# Module32Switches_SM.net
KiCad netlist of a schematic drawn in EasyEDA Pro
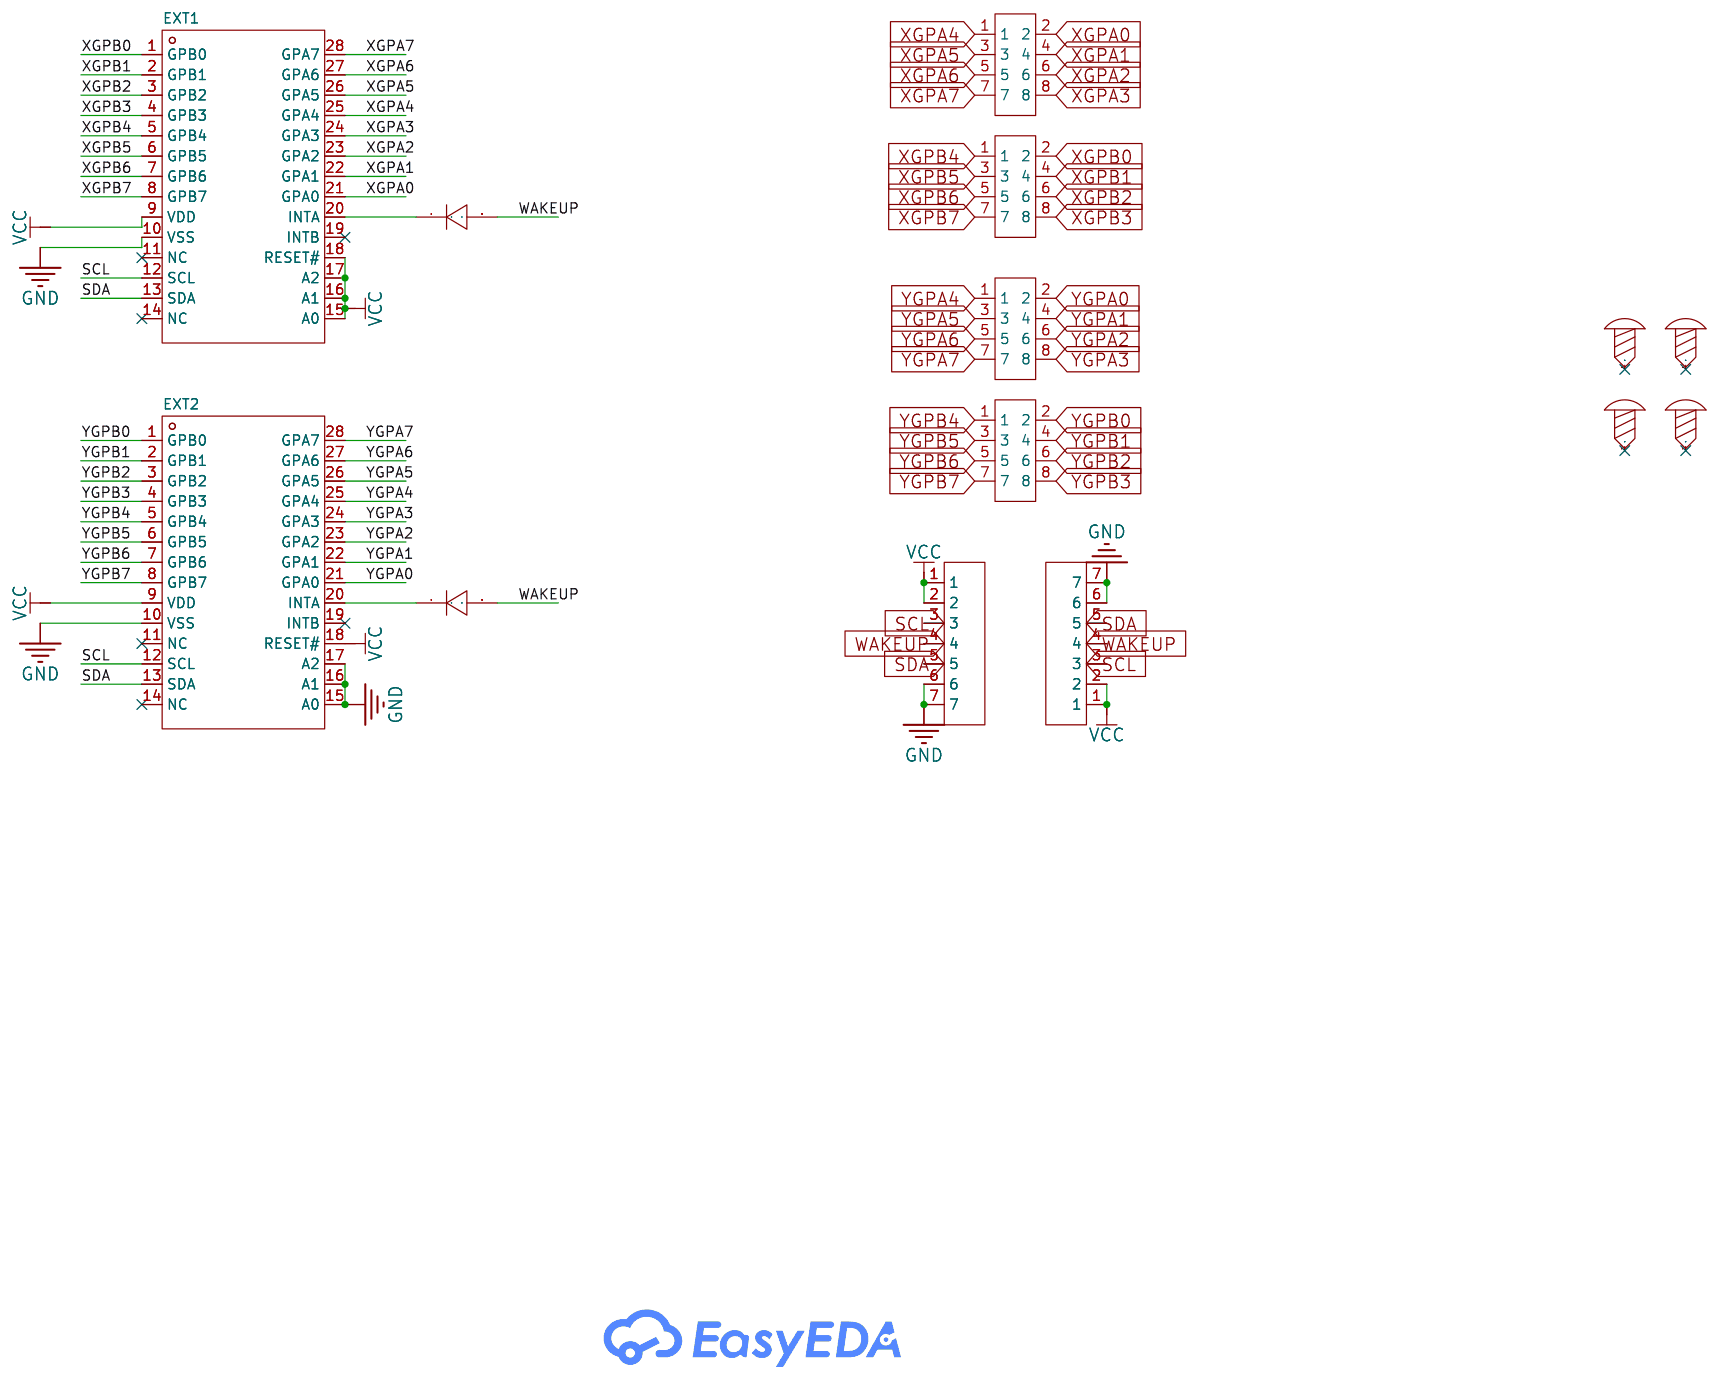
[diagram p0: schematic sheet]

(export (version "E")
  (design (tool "Eeschema 10.0.6"))
  (components
    (comp (ref "D1")
      (value "1N4148W")
      (footprint "easyedapro:SOD-123FL_L2.7-W1.6-LS3.8-RD")
      (fields (field (name "Manufacturer") "ST(先科)"))
      (libsource (lib "easyedapro") (part "1N4148W_C143180"))
    )
    (comp (ref "D2")
      (value "1N4148W")
      (footprint "easyedapro:SOD-123FL_L2.7-W1.6-LS3.8-RD")
      (fields (field (name "Manufacturer") "ST(先科)"))
      (libsource (lib "easyedapro") (part "1N4148W_C143180"))
    )
    (comp (ref "DEVKIT1")
      (value "~")
      (footprint "easyedapro:HDR-TH_7P-P2.54-V-M")
      (libsource (lib "easyedapro") (part "PZ254V-11-07P"))
    )
    (comp (ref "DEVKIT2")
      (value "~")
      (footprint "easyedapro:HDR-TH_7P-P2.54-V-M")
      (libsource (lib "easyedapro") (part "PZ254V-11-07P"))
    )
    (comp (ref "EXT1")
      (value "MCP23017T-E/ML")
      (footprint "easyedapro:SOIC-28_L18.0-W7.5-P1.27-LS10.3-BL")
      (fields (field (name "Manufacturer") "MICROCHIP(美国微芯)"))
      (libsource (lib "easyedapro") (part "MCP23017-E/SO"))
    )
    (comp (ref "EXT2")
      (value "MCP23017T-E/ML")
      (footprint "easyedapro:SOIC-28_L18.0-W7.5-P1.27-LS10.3-BL")
      (fields (field (name "Manufacturer") "MICROCHIP(美国微芯)"))
      (libsource (lib "easyedapro") (part "MCP23017-E/SO"))
    )
    (comp (ref "SCREW1")
      (value "~")
      (footprint "easyedapro:Screw-Hole-M2")
      (libsource (lib "easyedapro") (part "Screw-Hole"))
    )
    (comp (ref "SCREW2")
      (value "~")
      (footprint "easyedapro:Screw-Hole-M2")
      (libsource (lib "easyedapro") (part "Screw-Hole"))
    )
    (comp (ref "SCREW3")
      (value "~")
      (footprint "easyedapro:Screw-Hole-M2")
      (libsource (lib "easyedapro") (part "Screw-Hole"))
    )
    (comp (ref "SCREW4")
      (value "~")
      (footprint "easyedapro:Screw-Hole-M2")
      (libsource (lib "easyedapro") (part "Screw-Hole"))
    )
    (comp (ref "XH1")
      (value "PZ254R-12-8P")
      (footprint "easyedapro:HDR-TH_8P-P2.54-H-M-R2-C4-S2.54")
      (fields (field (name "Manufacturer") "XFCN(兴飞)"))
      (libsource (lib "easyedapro") (part "PZ254R-12-8P"))
    )
    (comp (ref "XH2")
      (value "PZ254R-12-8P")
      (footprint "easyedapro:HDR-TH_8P-P2.54-H-M-R2-C4-S2.54")
      (fields (field (name "Manufacturer") "XFCN(兴飞)"))
      (libsource (lib "easyedapro") (part "PZ254R-12-8P"))
    )
    (comp (ref "YH1")
      (value "PZ254R-12-8P")
      (footprint "easyedapro:HDR-TH_8P-P2.54-H-M-R2-C4-S2.54")
      (fields (field (name "Manufacturer") "XFCN(兴飞)"))
      (libsource (lib "easyedapro") (part "PZ254R-12-8P"))
    )
    (comp (ref "YH2")
      (value "PZ254R-12-8P")
      (footprint "easyedapro:HDR-TH_8P-P2.54-H-M-R2-C4-S2.54")
      (fields (field (name "Manufacturer") "XFCN(兴飞)"))
      (libsource (lib "easyedapro") (part "PZ254R-12-8P"))
    )
  )
  (nets
    (net (code "1") (name "GND") (class "Default")
      (node (ref "DEVKIT1") (pin "6") (pinfunction "6_6") (pintype "unspecified"))
      (node (ref "DEVKIT1") (pin "7") (pinfunction "7_7") (pintype "unspecified"))
      (node (ref "DEVKIT2") (pin "6") (pinfunction "6_6") (pintype "unspecified"))
      (node (ref "DEVKIT2") (pin "7") (pinfunction "7_7") (pintype "unspecified"))
      (node (ref "EXT1") (pin "10") (pinfunction "VSS_10") (pintype "unspecified"))
      (node (ref "EXT2") (pin "10") (pinfunction "VSS_10") (pintype "unspecified"))
      (node (ref "EXT2") (pin "15") (pinfunction "A0_15") (pintype "unspecified"))
      (node (ref "EXT2") (pin "16") (pinfunction "A1_16") (pintype "unspecified"))
      (node (ref "EXT2") (pin "17") (pinfunction "A2_17") (pintype "unspecified"))
    )
    (net (code "2") (name "Net-(D1-K)") (class "Default")
      (node (ref "D1") (pin "1") (pinfunction "K_1") (pintype "unspecified"))
      (node (ref "EXT1") (pin "20") (pinfunction "INTA_20") (pintype "unspecified"))
    )
    (net (code "3") (name "Net-(D2-K)") (class "Default")
      (node (ref "D2") (pin "1") (pinfunction "K_1") (pintype "unspecified"))
      (node (ref "EXT2") (pin "20") (pinfunction "INTA_20") (pintype "unspecified"))
    )
    (net (code "4") (name "SCL") (class "Default")
      (node (ref "DEVKIT1") (pin "3") (pinfunction "3_3") (pintype "unspecified"))
      (node (ref "DEVKIT2") (pin "3") (pinfunction "3_3") (pintype "unspecified"))
      (node (ref "EXT1") (pin "12") (pinfunction "SCL_12") (pintype "unspecified"))
      (node (ref "EXT2") (pin "12") (pinfunction "SCL_12") (pintype "unspecified"))
    )
    (net (code "5") (name "SDA") (class "Default")
      (node (ref "DEVKIT1") (pin "5") (pinfunction "5_5") (pintype "unspecified"))
      (node (ref "DEVKIT2") (pin "5") (pinfunction "5_5") (pintype "unspecified"))
      (node (ref "EXT1") (pin "13") (pinfunction "SDA_13") (pintype "unspecified"))
      (node (ref "EXT2") (pin "13") (pinfunction "SDA_13") (pintype "unspecified"))
    )
    (net (code "6") (name "VCC") (class "Default")
      (node (ref "DEVKIT1") (pin "1") (pinfunction "1_1") (pintype "unspecified"))
      (node (ref "DEVKIT1") (pin "2") (pinfunction "2_2") (pintype "unspecified"))
      (node (ref "DEVKIT2") (pin "1") (pinfunction "1_1") (pintype "unspecified"))
      (node (ref "DEVKIT2") (pin "2") (pinfunction "2_2") (pintype "unspecified"))
      (node (ref "EXT1") (pin "15") (pinfunction "A0_15") (pintype "unspecified"))
      (node (ref "EXT1") (pin "16") (pinfunction "A1_16") (pintype "unspecified"))
      (node (ref "EXT1") (pin "17") (pinfunction "A2_17") (pintype "unspecified"))
      (node (ref "EXT1") (pin "18") (pinfunction "RESET#_18") (pintype "unspecified"))
      (node (ref "EXT1") (pin "9") (pinfunction "VDD_9") (pintype "unspecified"))
      (node (ref "EXT2") (pin "18") (pinfunction "RESET#_18") (pintype "unspecified"))
      (node (ref "EXT2") (pin "9") (pinfunction "VDD_9") (pintype "unspecified"))
    )
    (net (code "7") (name "WAKEUP") (class "Default")
      (node (ref "D1") (pin "2") (pinfunction "A_2") (pintype "unspecified"))
      (node (ref "D2") (pin "2") (pinfunction "A_2") (pintype "unspecified"))
      (node (ref "DEVKIT1") (pin "4") (pinfunction "4_4") (pintype "unspecified"))
      (node (ref "DEVKIT2") (pin "4") (pinfunction "4_4") (pintype "unspecified"))
    )
    (net (code "8") (name "XGPA0") (class "Default")
      (node (ref "EXT1") (pin "21") (pinfunction "GPA0_21") (pintype "unspecified"))
      (node (ref "XH1") (pin "2") (pinfunction "2_2") (pintype "unspecified"))
    )
    (net (code "9") (name "XGPA1") (class "Default")
      (node (ref "EXT1") (pin "22") (pinfunction "GPA1_22") (pintype "unspecified"))
      (node (ref "XH1") (pin "4") (pinfunction "4_4") (pintype "unspecified"))
    )
    (net (code "10") (name "XGPA2") (class "Default")
      (node (ref "EXT1") (pin "23") (pinfunction "GPA2_23") (pintype "unspecified"))
      (node (ref "XH1") (pin "6") (pinfunction "6_6") (pintype "unspecified"))
    )
    (net (code "11") (name "XGPA3") (class "Default")
      (node (ref "EXT1") (pin "24") (pinfunction "GPA3_24") (pintype "unspecified"))
      (node (ref "XH1") (pin "8") (pinfunction "8_8") (pintype "unspecified"))
    )
    (net (code "12") (name "XGPA4") (class "Default")
      (node (ref "EXT1") (pin "25") (pinfunction "GPA4_25") (pintype "unspecified"))
      (node (ref "XH1") (pin "1") (pinfunction "1_1") (pintype "unspecified"))
    )
    (net (code "13") (name "XGPA5") (class "Default")
      (node (ref "EXT1") (pin "26") (pinfunction "GPA5_26") (pintype "unspecified"))
      (node (ref "XH1") (pin "3") (pinfunction "3_3") (pintype "unspecified"))
    )
    (net (code "14") (name "XGPA6") (class "Default")
      (node (ref "EXT1") (pin "27") (pinfunction "GPA6_27") (pintype "unspecified"))
      (node (ref "XH1") (pin "5") (pinfunction "5_5") (pintype "unspecified"))
    )
    (net (code "15") (name "XGPA7") (class "Default")
      (node (ref "EXT1") (pin "28") (pinfunction "GPA7_28") (pintype "unspecified"))
      (node (ref "XH1") (pin "7") (pinfunction "7_7") (pintype "unspecified"))
    )
    (net (code "16") (name "XGPB0") (class "Default")
      (node (ref "EXT1") (pin "1") (pinfunction "GPB0_1") (pintype "unspecified"))
      (node (ref "XH2") (pin "2") (pinfunction "2_2") (pintype "unspecified"))
    )
    (net (code "17") (name "XGPB1") (class "Default")
      (node (ref "EXT1") (pin "2") (pinfunction "GPB1_2") (pintype "unspecified"))
      (node (ref "XH2") (pin "4") (pinfunction "4_4") (pintype "unspecified"))
    )
    (net (code "18") (name "XGPB2") (class "Default")
      (node (ref "EXT1") (pin "3") (pinfunction "GPB2_3") (pintype "unspecified"))
      (node (ref "XH2") (pin "6") (pinfunction "6_6") (pintype "unspecified"))
    )
    (net (code "19") (name "XGPB3") (class "Default")
      (node (ref "EXT1") (pin "4") (pinfunction "GPB3_4") (pintype "unspecified"))
      (node (ref "XH2") (pin "8") (pinfunction "8_8") (pintype "unspecified"))
    )
    (net (code "20") (name "XGPB4") (class "Default")
      (node (ref "EXT1") (pin "5") (pinfunction "GPB4_5") (pintype "unspecified"))
      (node (ref "XH2") (pin "1") (pinfunction "1_1") (pintype "unspecified"))
    )
    (net (code "21") (name "XGPB5") (class "Default")
      (node (ref "EXT1") (pin "6") (pinfunction "GPB5_6") (pintype "unspecified"))
      (node (ref "XH2") (pin "3") (pinfunction "3_3") (pintype "unspecified"))
    )
    (net (code "22") (name "XGPB6") (class "Default")
      (node (ref "EXT1") (pin "7") (pinfunction "GPB6_7") (pintype "unspecified"))
      (node (ref "XH2") (pin "5") (pinfunction "5_5") (pintype "unspecified"))
    )
    (net (code "23") (name "XGPB7") (class "Default")
      (node (ref "EXT1") (pin "8") (pinfunction "GPB7_8") (pintype "unspecified"))
      (node (ref "XH2") (pin "7") (pinfunction "7_7") (pintype "unspecified"))
    )
    (net (code "24") (name "YGPA0") (class "Default")
      (node (ref "EXT2") (pin "21") (pinfunction "GPA0_21") (pintype "unspecified"))
      (node (ref "YH1") (pin "2") (pinfunction "2_2") (pintype "unspecified"))
    )
    (net (code "25") (name "YGPA1") (class "Default")
      (node (ref "EXT2") (pin "22") (pinfunction "GPA1_22") (pintype "unspecified"))
      (node (ref "YH1") (pin "4") (pinfunction "4_4") (pintype "unspecified"))
    )
    (net (code "26") (name "YGPA2") (class "Default")
      (node (ref "EXT2") (pin "23") (pinfunction "GPA2_23") (pintype "unspecified"))
      (node (ref "YH1") (pin "6") (pinfunction "6_6") (pintype "unspecified"))
    )
    (net (code "27") (name "YGPA3") (class "Default")
      (node (ref "EXT2") (pin "24") (pinfunction "GPA3_24") (pintype "unspecified"))
      (node (ref "YH1") (pin "8") (pinfunction "8_8") (pintype "unspecified"))
    )
    (net (code "28") (name "YGPA4") (class "Default")
      (node (ref "EXT2") (pin "25") (pinfunction "GPA4_25") (pintype "unspecified"))
      (node (ref "YH1") (pin "1") (pinfunction "1_1") (pintype "unspecified"))
    )
    (net (code "29") (name "YGPA5") (class "Default")
      (node (ref "EXT2") (pin "26") (pinfunction "GPA5_26") (pintype "unspecified"))
      (node (ref "YH1") (pin "3") (pinfunction "3_3") (pintype "unspecified"))
    )
    (net (code "30") (name "YGPA6") (class "Default")
      (node (ref "EXT2") (pin "27") (pinfunction "GPA6_27") (pintype "unspecified"))
      (node (ref "YH1") (pin "5") (pinfunction "5_5") (pintype "unspecified"))
    )
    (net (code "31") (name "YGPA7") (class "Default")
      (node (ref "EXT2") (pin "28") (pinfunction "GPA7_28") (pintype "unspecified"))
      (node (ref "YH1") (pin "7") (pinfunction "7_7") (pintype "unspecified"))
    )
    (net (code "32") (name "YGPB0") (class "Default")
      (node (ref "EXT2") (pin "1") (pinfunction "GPB0_1") (pintype "unspecified"))
      (node (ref "YH2") (pin "2") (pinfunction "2_2") (pintype "unspecified"))
    )
    (net (code "33") (name "YGPB1") (class "Default")
      (node (ref "EXT2") (pin "2") (pinfunction "GPB1_2") (pintype "unspecified"))
      (node (ref "YH2") (pin "4") (pinfunction "4_4") (pintype "unspecified"))
    )
    (net (code "34") (name "YGPB2") (class "Default")
      (node (ref "EXT2") (pin "3") (pinfunction "GPB2_3") (pintype "unspecified"))
      (node (ref "YH2") (pin "6") (pinfunction "6_6") (pintype "unspecified"))
    )
    (net (code "35") (name "YGPB3") (class "Default")
      (node (ref "EXT2") (pin "4") (pinfunction "GPB3_4") (pintype "unspecified"))
      (node (ref "YH2") (pin "8") (pinfunction "8_8") (pintype "unspecified"))
    )
    (net (code "36") (name "YGPB4") (class "Default")
      (node (ref "EXT2") (pin "5") (pinfunction "GPB4_5") (pintype "unspecified"))
      (node (ref "YH2") (pin "1") (pinfunction "1_1") (pintype "unspecified"))
    )
    (net (code "37") (name "YGPB5") (class "Default")
      (node (ref "EXT2") (pin "6") (pinfunction "GPB5_6") (pintype "unspecified"))
      (node (ref "YH2") (pin "3") (pinfunction "3_3") (pintype "unspecified"))
    )
    (net (code "38") (name "YGPB6") (class "Default")
      (node (ref "EXT2") (pin "7") (pinfunction "GPB6_7") (pintype "unspecified"))
      (node (ref "YH2") (pin "5") (pinfunction "5_5") (pintype "unspecified"))
    )
    (net (code "39") (name "YGPB7") (class "Default")
      (node (ref "EXT2") (pin "8") (pinfunction "GPB7_8") (pintype "unspecified"))
      (node (ref "YH2") (pin "7") (pinfunction "7_7") (pintype "unspecified"))
    )
    (net (code "40") (name "unconnected-(EXT1-INTB-Pad19)") (class "Default")
      (node (ref "EXT1") (pin "19") (pinfunction "INTB_19") (pintype "unspecified+no_connect"))
    )
    (net (code "41") (name "unconnected-(EXT1-NC-Pad11)") (class "Default")
      (node (ref "EXT1") (pin "11") (pinfunction "NC_11") (pintype "unspecified+no_connect"))
    )
    (net (code "42") (name "unconnected-(EXT1-NC-Pad14)") (class "Default")
      (node (ref "EXT1") (pin "14") (pinfunction "NC_14") (pintype "unspecified+no_connect"))
    )
    (net (code "43") (name "unconnected-(EXT2-INTB-Pad19)") (class "Default")
      (node (ref "EXT2") (pin "19") (pinfunction "INTB_19") (pintype "unspecified+no_connect"))
    )
    (net (code "44") (name "unconnected-(EXT2-NC-Pad11)") (class "Default")
      (node (ref "EXT2") (pin "11") (pinfunction "NC_11") (pintype "unspecified+no_connect"))
    )
    (net (code "45") (name "unconnected-(EXT2-NC-Pad14)") (class "Default")
      (node (ref "EXT2") (pin "14") (pinfunction "NC_14") (pintype "unspecified+no_connect"))
    )
    (net (code "46") (name "unconnected-(SCREW1-Pad1)") (class "Default")
      (node (ref "SCREW1") (pin "1") (pinfunction "1_1") (pintype "input+no_connect"))
    )
    (net (code "47") (name "unconnected-(SCREW2-Pad1)") (class "Default")
      (node (ref "SCREW2") (pin "1") (pinfunction "1_1") (pintype "input+no_connect"))
    )
    (net (code "48") (name "unconnected-(SCREW3-Pad1)") (class "Default")
      (node (ref "SCREW3") (pin "1") (pinfunction "1_1") (pintype "input+no_connect"))
    )
    (net (code "49") (name "unconnected-(SCREW4-Pad1)") (class "Default")
      (node (ref "SCREW4") (pin "1") (pinfunction "1_1") (pintype "input+no_connect"))
    )
  )
)
